# PAsignal_Genrator.net
KiCad netlist of a schematic drawn in Altium Designer
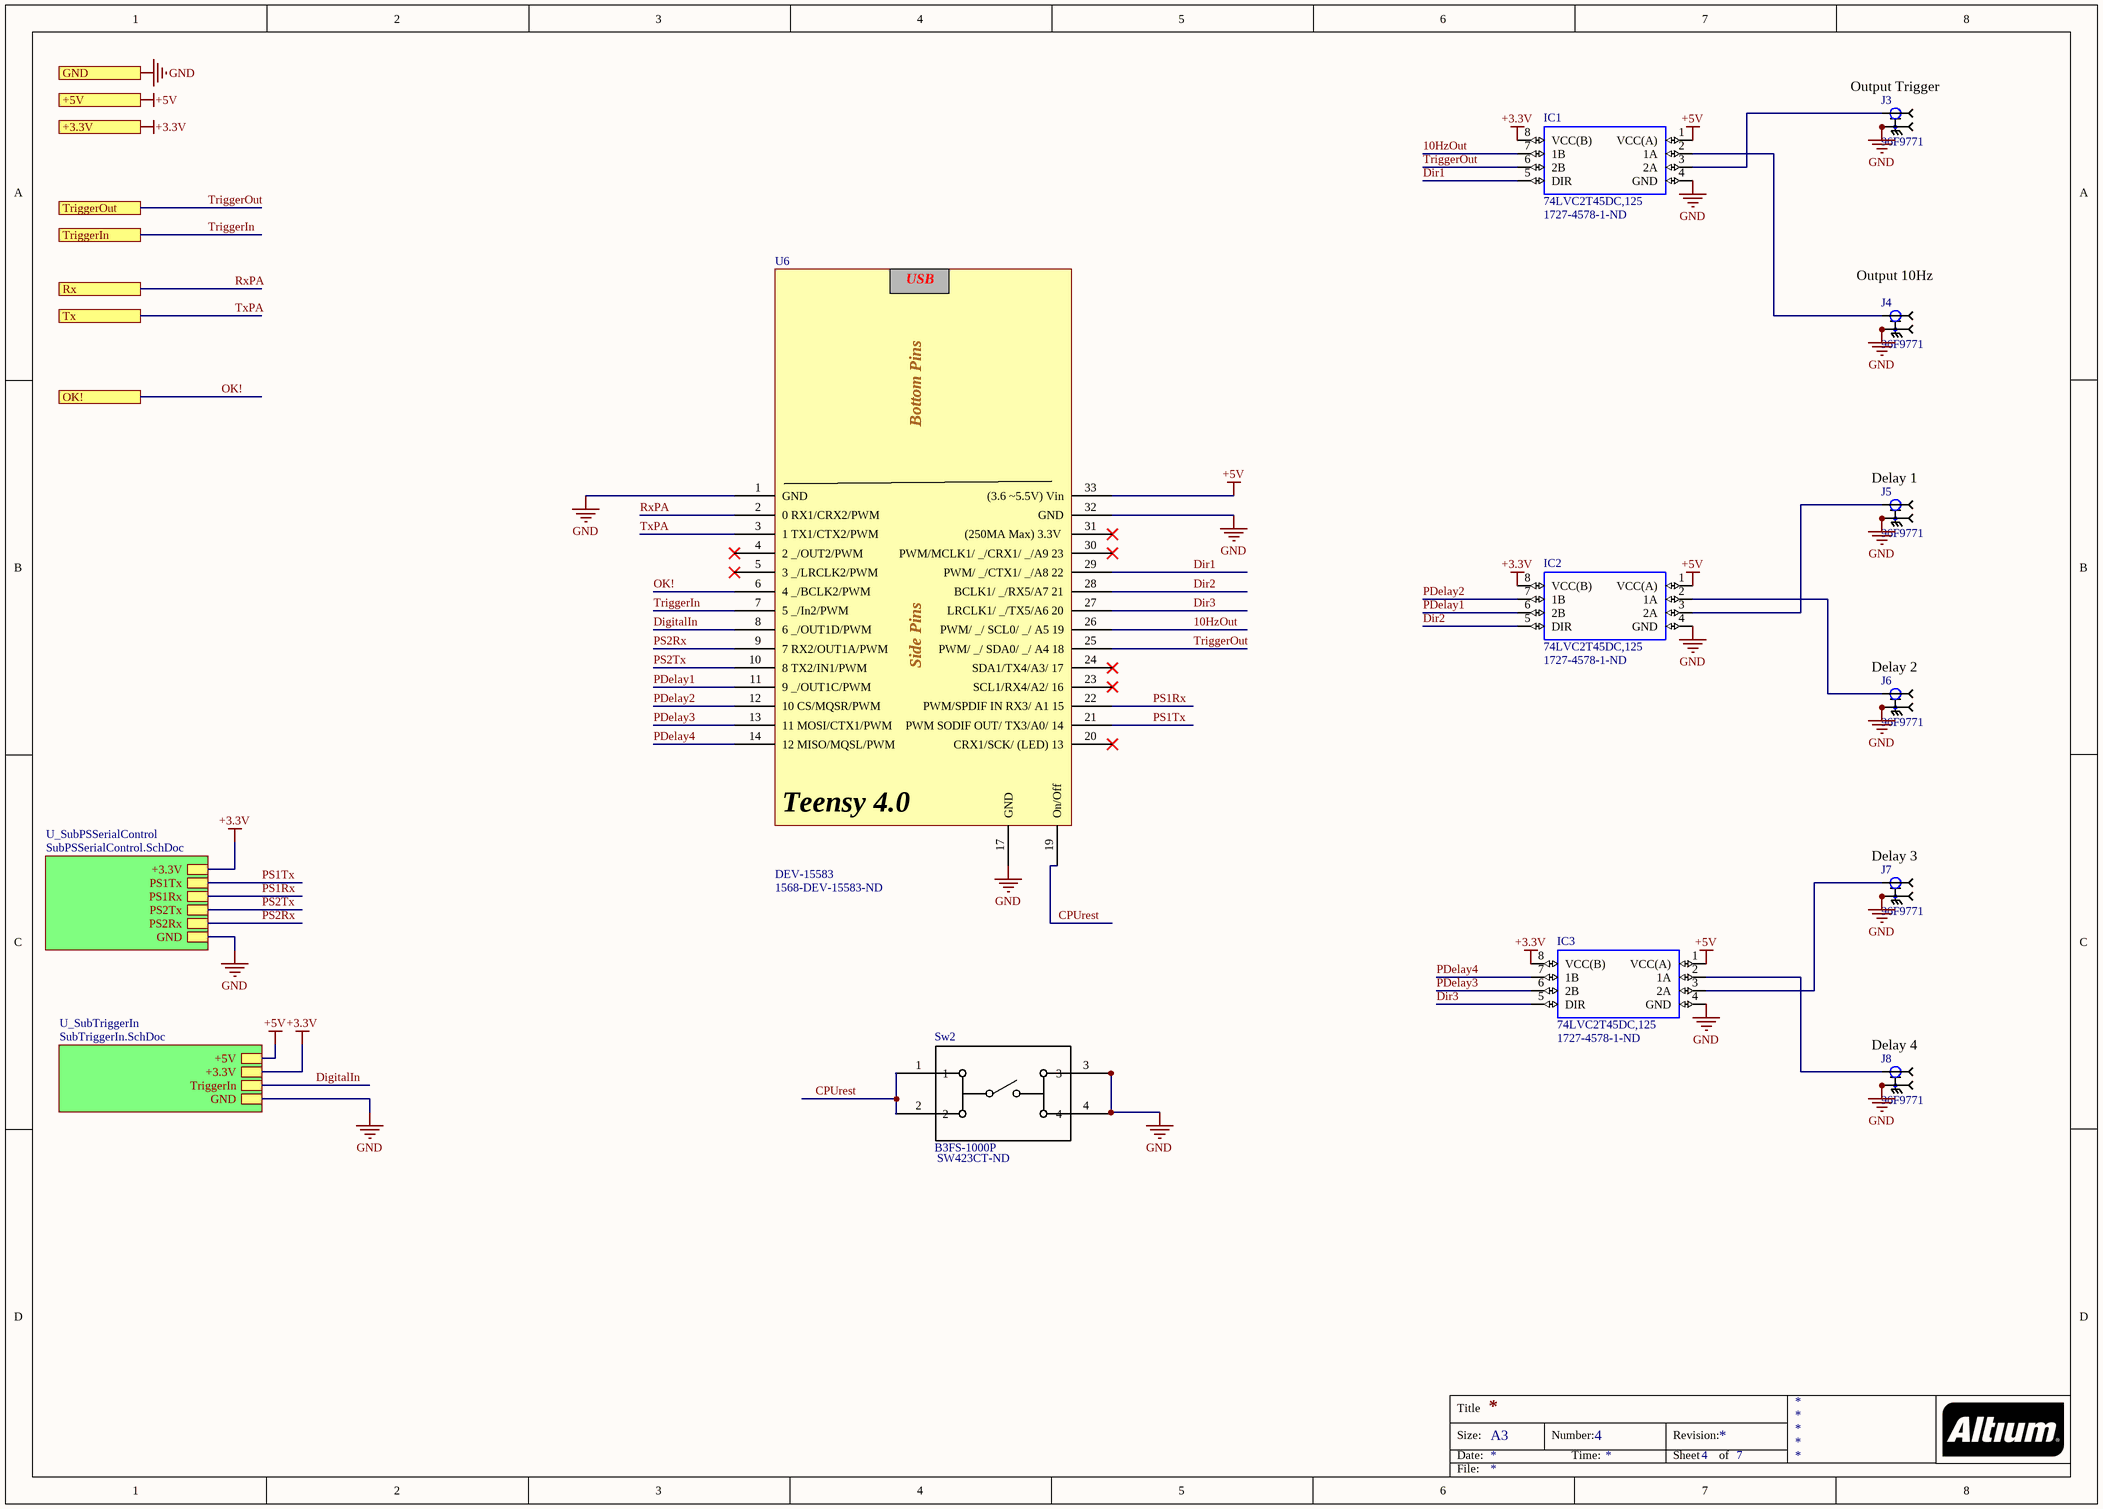
[diagram p0: PAsignal Genrator.SchDoc]

(export (version "E")
  (design (tool "Eeschema 10.0.6"))
  (components
    (comp (ref "IC1")
      (value "74LVC2T45DC,125")
      (footprint "SOP50P310X100-8N")
      (description "Voltage Level Translator Bidirectional 1 Circuit 2 Channel 420Mbps 8-VSSOP")
      (fields (field (name "MF") "Nexperia USA") (field (name "SUPPLIER PART NUMBER 1") "1727-4578-1-ND"))
      (libsource (lib "Afshin Library") (part "74LVC2T45DC,125"))
    )
    (comp (ref "IC2")
      (value "74LVC2T45DC,125")
      (footprint "SOP50P310X100-8N")
      (description "Voltage Level Translator Bidirectional 1 Circuit 2 Channel 420Mbps 8-VSSOP")
      (fields (field (name "MF") "Nexperia USA") (field (name "SUPPLIER PART NUMBER 1") "1727-4578-1-ND"))
      (libsource (lib "Afshin Library") (part "74LVC2T45DC,125"))
    )
    (comp (ref "IC3")
      (value "74LVC2T45DC,125")
      (footprint "SOP50P310X100-8N")
      (description "Voltage Level Translator Bidirectional 1 Circuit 2 Channel 420Mbps 8-VSSOP")
      (fields (field (name "MF") "Nexperia USA") (field (name "SUPPLIER PART NUMBER 1") "1727-4578-1-ND"))
      (libsource (lib "Afshin Library") (part "74LVC2T45DC,125"))
    )
    (comp (ref "J3")
      (value "131-3701-801")
      (footprint "SMBboardEdge")
      (description "SMB Connector Jack, Male Pin 50Ohm Board Edge, End Launch Solder")
      (fields (field (name "SUPPLIER PART NUMBER 1") "96F9771"))
      (libsource (lib "Afshin Library") (part "SMB"))
    )
    (comp (ref "J4")
      (value "131-3701-801")
      (footprint "SMBboardEdge")
      (description "SMB Connector Jack, Male Pin 50Ohm Board Edge, End Launch Solder")
      (fields (field (name "SUPPLIER PART NUMBER 1") "96F9771"))
      (libsource (lib "Afshin Library") (part "SMB"))
    )
    (comp (ref "J5")
      (value "131-3701-801")
      (footprint "SMBboardEdge")
      (description "SMB Connector Jack, Male Pin 50Ohm Board Edge, End Launch Solder")
      (fields (field (name "SUPPLIER PART NUMBER 1") "96F9771"))
      (libsource (lib "Afshin Library") (part "SMB"))
    )
    (comp (ref "J6")
      (value "131-3701-801")
      (footprint "SMBboardEdge")
      (description "SMB Connector Jack, Male Pin 50Ohm Board Edge, End Launch Solder")
      (fields (field (name "SUPPLIER PART NUMBER 1") "96F9771"))
      (libsource (lib "Afshin Library") (part "SMB"))
    )
    (comp (ref "J7")
      (value "131-3701-801")
      (footprint "SMBboardEdge")
      (description "SMB Connector Jack, Male Pin 50Ohm Board Edge, End Launch Solder")
      (fields (field (name "SUPPLIER PART NUMBER 1") "96F9771"))
      (libsource (lib "Afshin Library") (part "SMB"))
    )
    (comp (ref "J8")
      (value "131-3701-801")
      (footprint "SMBboardEdge")
      (description "SMB Connector Jack, Male Pin 50Ohm Board Edge, End Launch Solder")
      (fields (field (name "SUPPLIER PART NUMBER 1") "96F9771"))
      (libsource (lib "Afshin Library") (part "SMB"))
    )
    (comp (ref "Sw2")
      (value "B3FS-1000P")
      (footprint "B3FS-1000P")
      (description "Tactile Switch SPST-NO Top Actuated Surface Mount")
      (fields (field (name "SUPPLIER PART NUMBER 1") "SW423CT-ND"))
      (libsource (lib "Afshin Library") (part "B3FS-1000P"))
    )
    (comp (ref "U6")
      (value "DEV-15583")
      (footprint "Teensy 4.0sideOnly")
      (fields (field (name "SUPPLIER PART NUMBER 1") "1568-DEV-15583-ND"))
      (libsource (lib "Afshin Library") (part "Teensy 4.0_SideOnly"))
    )
  )
  (nets
    (net (code "1") (name "+3.3V") (class "Default")
      (node (ref "IC1") (pin "8") (pinfunction "VCC(B)_8") (pintype "bidirectional"))
      (node (ref "IC2") (pin "8") (pinfunction "VCC(B)_8") (pintype "bidirectional"))
      (node (ref "IC3") (pin "8") (pinfunction "VCC(B)_8") (pintype "bidirectional"))
    )
    (net (code "2") (name "+5V") (class "Default")
      (node (ref "IC1") (pin "1") (pinfunction "VCC(A)_1") (pintype "bidirectional"))
      (node (ref "IC2") (pin "1") (pinfunction "VCC(A)_1") (pintype "bidirectional"))
      (node (ref "IC3") (pin "1") (pinfunction "VCC(A)_1") (pintype "bidirectional"))
      (node (ref "U6") (pin "33") (pinfunction "(3.6_~5.5V)_Vin_33") (pintype "passive"))
    )
    (net (code "3") (name "/10HzOut") (class "Default")
      (node (ref "IC1") (pin "7") (pinfunction "1B_7") (pintype "bidirectional"))
      (node (ref "U6") (pin "26") (pinfunction "PWM/__/_SCL0/__/_A5_19_26") (pintype "passive"))
    )
    (net (code "4") (name "/CPUrest") (class "Default")
      (node (ref "Sw2") (pin "1") (pinfunction "1_1") (pintype "passive"))
      (node (ref "Sw2") (pin "2") (pinfunction "2_2") (pintype "passive"))
      (node (ref "U6") (pin "19") (pinfunction "On/Off_19") (pintype "passive"))
    )
    (net (code "5") (name "/DigitalIn") (class "Default")
      (node (ref "U6") (pin "8") (pinfunction "6__/OUT1D/PWM_8") (pintype "passive"))
    )
    (net (code "6") (name "/Dir1") (class "Default")
      (node (ref "IC1") (pin "5") (pinfunction "DIR_5") (pintype "bidirectional"))
      (node (ref "U6") (pin "29") (pinfunction "PWM/__/CTX1/__/A8_22_29") (pintype "passive"))
    )
    (net (code "7") (name "/Dir2") (class "Default")
      (node (ref "IC2") (pin "5") (pinfunction "DIR_5") (pintype "bidirectional"))
      (node (ref "U6") (pin "28") (pinfunction "BCLK1/__/RX5/A7_21_28") (pintype "passive"))
    )
    (net (code "8") (name "/Dir3") (class "Default")
      (node (ref "IC3") (pin "5") (pinfunction "DIR_5") (pintype "bidirectional"))
      (node (ref "U6") (pin "27") (pinfunction "LRCLK1/__/TX5/A6_20_27") (pintype "passive"))
    )
    (net (code "9") (name "/OK!") (class "Default")
      (node (ref "U6") (pin "6") (pinfunction "4__/BCLK2/PWM_6") (pintype "passive"))
    )
    (net (code "10") (name "/PDelay1") (class "Default")
      (node (ref "IC2") (pin "6") (pinfunction "2B_6") (pintype "bidirectional"))
      (node (ref "U6") (pin "11") (pinfunction "9__/OUT1C/PWM_11") (pintype "passive"))
    )
    (net (code "11") (name "/PDelay2") (class "Default")
      (node (ref "IC2") (pin "7") (pinfunction "1B_7") (pintype "bidirectional"))
      (node (ref "U6") (pin "12") (pinfunction "10_CS/MQSR/PWM_12") (pintype "passive"))
    )
    (net (code "12") (name "/PDelay3") (class "Default")
      (node (ref "IC3") (pin "6") (pinfunction "2B_6") (pintype "bidirectional"))
      (node (ref "U6") (pin "13") (pinfunction "11_MOSI/CTX1/PWM_13") (pintype "passive"))
    )
    (net (code "13") (name "/PDelay4") (class "Default")
      (node (ref "IC3") (pin "7") (pinfunction "1B_7") (pintype "bidirectional"))
      (node (ref "U6") (pin "14") (pinfunction "12_MISO/MQSL/PWM_14") (pintype "passive"))
    )
    (net (code "14") (name "/PS1Rx") (class "Default")
      (node (ref "U6") (pin "22") (pinfunction "PWM/SPDIF_IN_RX3/_A1_15_22") (pintype "passive"))
    )
    (net (code "15") (name "/PS1Tx") (class "Default")
      (node (ref "U6") (pin "21") (pinfunction "PWM_SODIF_OUT/_TX3/A0/_14_21") (pintype "passive"))
    )
    (net (code "16") (name "/PS2Rx") (class "Default")
      (node (ref "U6") (pin "9") (pinfunction "7_RX2/OUT1A/PWM_9") (pintype "passive"))
    )
    (net (code "17") (name "/PS2Tx") (class "Default")
      (node (ref "U6") (pin "10") (pinfunction "8_TX2/IN1/PWM_10") (pintype "passive"))
    )
    (net (code "18") (name "/RxPA") (class "Default")
      (node (ref "U6") (pin "2") (pinfunction "0_RX1/CRX2/PWM_2") (pintype "passive"))
    )
    (net (code "19") (name "/TriggerIn") (class "Default")
      (node (ref "U6") (pin "7") (pinfunction "5__/In2/PWM_7") (pintype "passive"))
    )
    (net (code "20") (name "/TriggerOut") (class "Default")
      (node (ref "IC1") (pin "6") (pinfunction "2B_6") (pintype "bidirectional"))
      (node (ref "U6") (pin "25") (pinfunction "PWM/__/_SDA0/__/_A4_18_25") (pintype "passive"))
    )
    (net (code "21") (name "/TxPA") (class "Default")
      (node (ref "U6") (pin "3") (pinfunction "1_TX1/CTX2/PWM_3") (pintype "passive"))
    )
    (net (code "22") (name "GND") (class "Default")
      (node (ref "IC1") (pin "4") (pinfunction "GND_4") (pintype "bidirectional"))
      (node (ref "IC2") (pin "4") (pinfunction "GND_4") (pintype "bidirectional"))
      (node (ref "IC3") (pin "4") (pinfunction "GND_4") (pintype "bidirectional"))
      (node (ref "J3") (pin "SH1") (pinfunction "2_SH1") (pintype "passive"))
      (node (ref "J3") (pin "SH2") (pinfunction "2_SH2") (pintype "passive"))
      (node (ref "J3") (pin "SH3") (pinfunction "2_SH3") (pintype "passive"))
      (node (ref "J3") (pin "SH4") (pinfunction "2_SH4") (pintype "passive"))
      (node (ref "J4") (pin "SH1") (pinfunction "2_SH1") (pintype "passive"))
      (node (ref "J4") (pin "SH2") (pinfunction "2_SH2") (pintype "passive"))
      (node (ref "J4") (pin "SH3") (pinfunction "2_SH3") (pintype "passive"))
      (node (ref "J4") (pin "SH4") (pinfunction "2_SH4") (pintype "passive"))
      (node (ref "J5") (pin "SH1") (pinfunction "2_SH1") (pintype "passive"))
      (node (ref "J5") (pin "SH2") (pinfunction "2_SH2") (pintype "passive"))
      (node (ref "J5") (pin "SH3") (pinfunction "2_SH3") (pintype "passive"))
      (node (ref "J5") (pin "SH4") (pinfunction "2_SH4") (pintype "passive"))
      (node (ref "J6") (pin "SH1") (pinfunction "2_SH1") (pintype "passive"))
      (node (ref "J6") (pin "SH2") (pinfunction "2_SH2") (pintype "passive"))
      (node (ref "J6") (pin "SH3") (pinfunction "2_SH3") (pintype "passive"))
      (node (ref "J6") (pin "SH4") (pinfunction "2_SH4") (pintype "passive"))
      (node (ref "J7") (pin "SH1") (pinfunction "2_SH1") (pintype "passive"))
      (node (ref "J7") (pin "SH2") (pinfunction "2_SH2") (pintype "passive"))
      (node (ref "J7") (pin "SH3") (pinfunction "2_SH3") (pintype "passive"))
      (node (ref "J7") (pin "SH4") (pinfunction "2_SH4") (pintype "passive"))
      (node (ref "J8") (pin "SH1") (pinfunction "2_SH1") (pintype "passive"))
      (node (ref "J8") (pin "SH2") (pinfunction "2_SH2") (pintype "passive"))
      (node (ref "J8") (pin "SH3") (pinfunction "2_SH3") (pintype "passive"))
      (node (ref "J8") (pin "SH4") (pinfunction "2_SH4") (pintype "passive"))
      (node (ref "Sw2") (pin "3") (pinfunction "3_3") (pintype "passive"))
      (node (ref "Sw2") (pin "4") (pinfunction "4_4") (pintype "passive"))
      (node (ref "U6") (pin "1") (pinfunction "GND_1") (pintype "passive"))
      (node (ref "U6") (pin "17") (pinfunction "GND_17") (pintype "passive"))
      (node (ref "U6") (pin "32") (pinfunction "GND_32") (pintype "passive"))
    )
    (net (code "23") (name "Net-(IC1-1A)") (class "Default")
      (node (ref "IC1") (pin "2") (pinfunction "1A_2") (pintype "bidirectional"))
      (node (ref "J4") (pin "1") (pinfunction "1_1") (pintype "passive"))
    )
    (net (code "24") (name "Net-(IC1-2A)") (class "Default")
      (node (ref "IC1") (pin "3") (pinfunction "2A_3") (pintype "bidirectional"))
      (node (ref "J3") (pin "1") (pinfunction "1_1") (pintype "passive"))
    )
    (net (code "25") (name "Net-(IC2-1A)") (class "Default")
      (node (ref "IC2") (pin "2") (pinfunction "1A_2") (pintype "bidirectional"))
      (node (ref "J6") (pin "1") (pinfunction "1_1") (pintype "passive"))
    )
    (net (code "26") (name "Net-(IC2-2A)") (class "Default")
      (node (ref "IC2") (pin "3") (pinfunction "2A_3") (pintype "bidirectional"))
      (node (ref "J5") (pin "1") (pinfunction "1_1") (pintype "passive"))
    )
    (net (code "27") (name "Net-(IC3-1A)") (class "Default")
      (node (ref "IC3") (pin "2") (pinfunction "1A_2") (pintype "bidirectional"))
      (node (ref "J8") (pin "1") (pinfunction "1_1") (pintype "passive"))
    )
    (net (code "28") (name "Net-(IC3-2A)") (class "Default")
      (node (ref "IC3") (pin "3") (pinfunction "2A_3") (pintype "bidirectional"))
      (node (ref "J7") (pin "1") (pinfunction "1_1") (pintype "passive"))
    )
    (net (code "29") (name "unconnected-(U6-(250MA_Max)_3.3V-Pad31)") (class "Default")
      (node (ref "U6") (pin "31") (pinfunction "(250MA_Max)_3.3V_31") (pintype "passive+no_connect"))
    )
    (net (code "30") (name "unconnected-(U6-2__{slash}OUT2{slash}PWM-Pad4)") (class "Default")
      (node (ref "U6") (pin "4") (pinfunction "2__/OUT2/PWM_4") (pintype "passive+no_connect"))
    )
    (net (code "31") (name "unconnected-(U6-3__{slash}LRCLK2{slash}PWM-Pad5)") (class "Default")
      (node (ref "U6") (pin "5") (pinfunction "3__/LRCLK2/PWM_5") (pintype "passive+no_connect"))
    )
    (net (code "32") (name "unconnected-(U6-CRX1{slash}SCK{slash}_(LED)_13-Pad20)") (class "Default")
      (node (ref "U6") (pin "20") (pinfunction "CRX1/SCK/_(LED)_13_20") (pintype "passive+no_connect"))
    )
    (net (code "33") (name "unconnected-(U6-PWM{slash}MCLK1{slash}__{slash}CRX1{slash}__{slash}A9_23-Pad30)") (class "Default")
      (node (ref "U6") (pin "30") (pinfunction "PWM/MCLK1/__/CRX1/__/A9_23_30") (pintype "passive+no_connect"))
    )
    (net (code "34") (name "unconnected-(U6-SCL1{slash}RX4{slash}A2{slash}_16-Pad23)") (class "Default")
      (node (ref "U6") (pin "23") (pinfunction "SCL1/RX4/A2/_16_23") (pintype "passive+no_connect"))
    )
    (net (code "35") (name "unconnected-(U6-SDA1{slash}TX4{slash}A3{slash}_17-Pad24)") (class "Default")
      (node (ref "U6") (pin "24") (pinfunction "SDA1/TX4/A3/_17_24") (pintype "passive+no_connect"))
    )
  )
)
